# Duplexer.net
KiCad netlist of a schematic drawn in Altium Designer
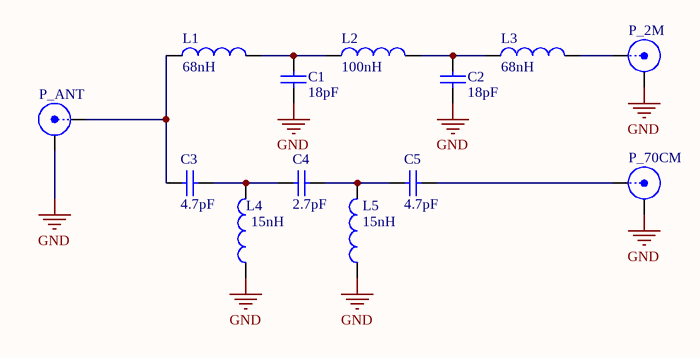
[diagram p0: Duplexer.SchDoc]

(export (version "E")
  (design (tool "Eeschema 10.0.6"))
  (components
    (comp (ref "C1")
      (value "18pF")
      (footprint "6-0805_N")
      (description "Capacitor (Semiconductor SIM Model)")
      (fields (field (name "Comment") "Cap Semi") (field (name "PUBLISHER") "Altium Limited"))
      (libsource (lib "Miscellaneous Devices") (part "Cap Semi"))
    )
    (comp (ref "C2")
      (value "18pF")
      (footprint "6-0805_N")
      (description "Capacitor (Semiconductor SIM Model)")
      (fields (field (name "Comment") "Cap Semi") (field (name "PUBLISHER") "Altium Limited"))
      (libsource (lib "Miscellaneous Devices") (part "Cap Semi"))
    )
    (comp (ref "C3")
      (value "4.7pF")
      (footprint "6-0805_N")
      (description "Capacitor (Semiconductor SIM Model)")
      (fields (field (name "Comment") "Cap Semi") (field (name "PUBLISHER") "Altium Limited"))
      (libsource (lib "Miscellaneous Devices") (part "Cap Semi"))
    )
    (comp (ref "C4")
      (value "2.7pF")
      (footprint "6-0805_N")
      (description "Capacitor (Semiconductor SIM Model)")
      (fields (field (name "Comment") "Cap Semi") (field (name "PUBLISHER") "Altium Limited"))
      (libsource (lib "Miscellaneous Devices") (part "Cap Semi"))
    )
    (comp (ref "C5")
      (value "4.7pF")
      (footprint "6-0805_N")
      (description "Capacitor (Semiconductor SIM Model)")
      (fields (field (name "Comment") "Cap Semi") (field (name "PUBLISHER") "Altium Limited"))
      (libsource (lib "Miscellaneous Devices") (part "Cap Semi"))
    )
    (comp (ref "L1")
      (value "68nH")
      (footprint "6-0805_N")
      (description "Inductor")
      (fields (field (name "PUBLISHER") "Altium Limited"))
      (libsource (lib "Miscellaneous Devices") (part "Inductor"))
    )
    (comp (ref "L2")
      (value "100nH")
      (footprint "6-0805_N")
      (description "Inductor")
      (fields (field (name "PUBLISHER") "Altium Limited"))
      (libsource (lib "Miscellaneous Devices") (part "Inductor"))
    )
    (comp (ref "L3")
      (value "68nH")
      (footprint "6-0805_N")
      (description "Inductor")
      (fields (field (name "PUBLISHER") "Altium Limited"))
      (libsource (lib "Miscellaneous Devices") (part "Inductor"))
    )
    (comp (ref "L4")
      (value "15nH")
      (footprint "6-0805_N")
      (description "Inductor")
      (fields (field (name "PUBLISHER") "Altium Limited"))
      (libsource (lib "Miscellaneous Devices") (part "Inductor"))
    )
    (comp (ref "L5")
      (value "15nH")
      (footprint "6-0805_N")
      (description "Inductor")
      (fields (field (name "PUBLISHER") "Altium Limited"))
      (libsource (lib "Miscellaneous Devices") (part "Inductor"))
    )
    (comp (ref "P_2M")
      (value "SMB")
      (footprint "SMB_V-RJ45")
      (description "SMB Straight Connector")
      (fields (field (name "PUBLISHER") "Altium Limited"))
      (libsource (lib "Miscellaneous Connectors") (part "SMB"))
    )
    (comp (ref "P_70CM")
      (value "SMB")
      (footprint "SMB_V-RJ45")
      (description "SMB Straight Connector")
      (fields (field (name "PUBLISHER") "Altium Limited"))
      (libsource (lib "Miscellaneous Connectors") (part "SMB"))
    )
    (comp (ref "P_ANT")
      (value "SMB")
      (footprint "SMB_V-RJ45")
      (description "SMB Straight Connector")
      (fields (field (name "PUBLISHER") "Altium Limited"))
      (libsource (lib "Miscellaneous Connectors") (part "SMB"))
    )
  )
  (nets
    (net (code "1") (name "GND") (class "Default")
      (node (ref "C1") (pin "1") (pinfunction "1_1") (pintype "passive"))
      (node (ref "C2") (pin "1") (pinfunction "1_1") (pintype "passive"))
      (node (ref "L4") (pin "1") (pinfunction "1_1") (pintype "passive"))
      (node (ref "L5") (pin "1") (pinfunction "1_1") (pintype "passive"))
      (node (ref "P_2M") (pin "2") (pinfunction "Y_2") (pintype "passive"))
      (node (ref "P_70CM") (pin "2") (pinfunction "Y_2") (pintype "passive"))
      (node (ref "P_ANT") (pin "2") (pinfunction "Y_2") (pintype "passive"))
    )
    (net (code "2") (name "Net-(C1-Pad2)") (class "Default")
      (node (ref "C1") (pin "2") (pinfunction "2_2") (pintype "passive"))
      (node (ref "L1") (pin "2") (pinfunction "2_2") (pintype "passive"))
      (node (ref "L2") (pin "1") (pinfunction "1_1") (pintype "passive"))
    )
    (net (code "3") (name "Net-(C2-Pad2)") (class "Default")
      (node (ref "C2") (pin "2") (pinfunction "2_2") (pintype "passive"))
      (node (ref "L2") (pin "2") (pinfunction "2_2") (pintype "passive"))
      (node (ref "L3") (pin "1") (pinfunction "1_1") (pintype "passive"))
    )
    (net (code "4") (name "Net-(C3-Pad1)") (class "Default")
      (node (ref "C3") (pin "1") (pinfunction "1_1") (pintype "passive"))
      (node (ref "C4") (pin "2") (pinfunction "2_2") (pintype "passive"))
      (node (ref "L4") (pin "2") (pinfunction "2_2") (pintype "passive"))
    )
    (net (code "5") (name "Net-(C4-Pad1)") (class "Default")
      (node (ref "C4") (pin "1") (pinfunction "1_1") (pintype "passive"))
      (node (ref "C5") (pin "2") (pinfunction "2_2") (pintype "passive"))
      (node (ref "L5") (pin "2") (pinfunction "2_2") (pintype "passive"))
    )
    (net (code "6") (name "Net-(P_2M-X)") (class "Default")
      (node (ref "L3") (pin "2") (pinfunction "2_2") (pintype "passive"))
      (node (ref "P_2M") (pin "1") (pinfunction "X_1") (pintype "passive"))
    )
    (net (code "7") (name "Net-(P_70CM-X)") (class "Default")
      (node (ref "C5") (pin "1") (pinfunction "1_1") (pintype "passive"))
      (node (ref "P_70CM") (pin "1") (pinfunction "X_1") (pintype "passive"))
    )
    (net (code "8") (name "Net-(P_ANT-X)") (class "Default")
      (node (ref "C3") (pin "2") (pinfunction "2_2") (pintype "passive"))
      (node (ref "L1") (pin "1") (pinfunction "1_1") (pintype "passive"))
      (node (ref "P_ANT") (pin "1") (pinfunction "X_1") (pintype "passive"))
    )
  )
)
